# Sheet1.net
KiCad netlist of a schematic drawn in Altium Designer
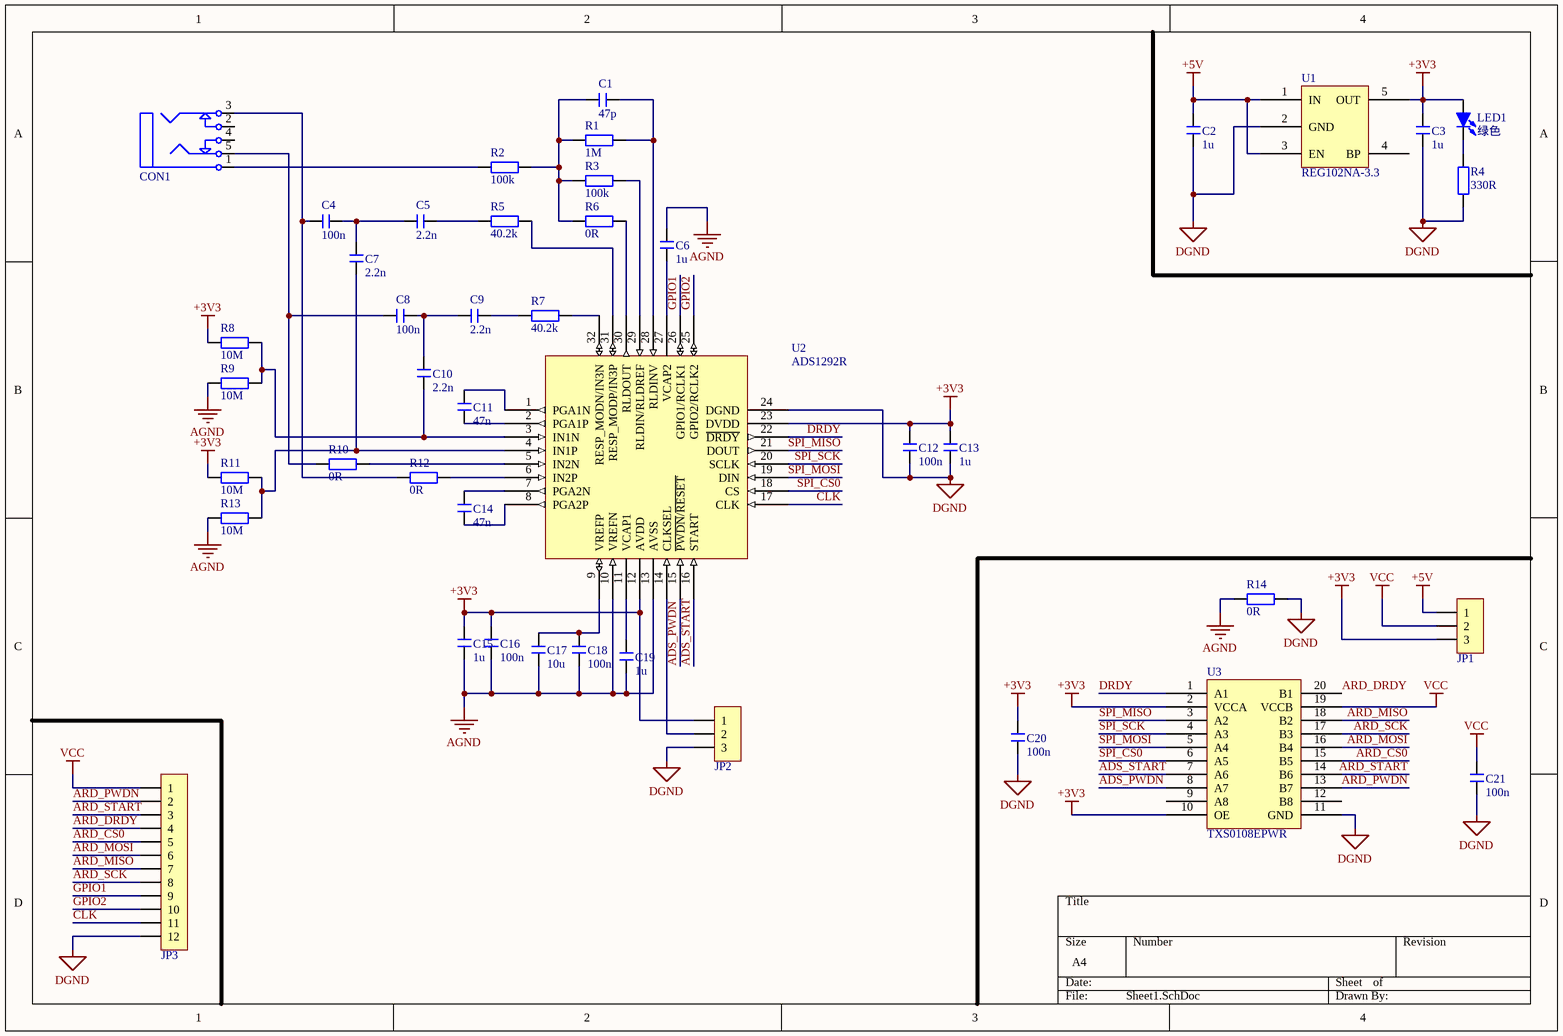
[diagram p0: Sheet1.SchDoc]

(export (version "E")
  (design (tool "Eeschema 10.0.6"))
  (components
    (comp (ref "C1")
      (value "47p")
      (footprint "C 0805_L")
      (description "无极性贴片电容")
      (fields (field (name "版权归属") "源创客"))
      (libsource (lib "3.1   - 电阻-电容-电感") (part "C"))
    )
    (comp (ref "C2")
      (value "1u")
      (footprint "C 0805_L")
      (description "无极性贴片电容")
      (fields (field (name "版权归属") "源创客"))
      (libsource (lib "3.1   - 电阻-电容-电感") (part "C"))
    )
    (comp (ref "C3")
      (value "1u")
      (footprint "C 0805_L")
      (description "无极性贴片电容")
      (fields (field (name "版权归属") "源创客"))
      (libsource (lib "3.1   - 电阻-电容-电感") (part "C"))
    )
    (comp (ref "C4")
      (value "100n")
      (footprint "C 0805_L")
      (description "无极性贴片电容")
      (fields (field (name "版权归属") "源创客"))
      (libsource (lib "3.1   - 电阻-电容-电感") (part "C"))
    )
    (comp (ref "C5")
      (value "2.2n")
      (footprint "C 0805_L")
      (description "无极性贴片电容")
      (fields (field (name "版权归属") "源创客"))
      (libsource (lib "3.1   - 电阻-电容-电感") (part "C"))
    )
    (comp (ref "C6")
      (value "1u")
      (footprint "C 0805_L")
      (description "无极性贴片电容")
      (fields (field (name "版权归属") "源创客"))
      (libsource (lib "3.1   - 电阻-电容-电感") (part "C"))
    )
    (comp (ref "C7")
      (value "2.2n")
      (footprint "C 0805_L")
      (description "无极性贴片电容")
      (fields (field (name "版权归属") "源创客"))
      (libsource (lib "3.1   - 电阻-电容-电感") (part "C"))
    )
    (comp (ref "C8")
      (value "100n")
      (footprint "C 0805_L")
      (description "无极性贴片电容")
      (fields (field (name "版权归属") "源创客"))
      (libsource (lib "3.1   - 电阻-电容-电感") (part "C"))
    )
    (comp (ref "C9")
      (value "2.2n")
      (footprint "C 0805_L")
      (description "无极性贴片电容")
      (fields (field (name "版权归属") "源创客"))
      (libsource (lib "3.1   - 电阻-电容-电感") (part "C"))
    )
    (comp (ref "C10")
      (value "2.2n")
      (footprint "C 0805_L")
      (description "无极性贴片电容")
      (fields (field (name "版权归属") "源创客"))
      (libsource (lib "3.1   - 电阻-电容-电感") (part "C"))
    )
    (comp (ref "C11")
      (value "47n")
      (footprint "C 0805_L")
      (description "无极性贴片电容")
      (fields (field (name "版权归属") "源创客"))
      (libsource (lib "3.1   - 电阻-电容-电感") (part "C"))
    )
    (comp (ref "C12")
      (value "100n")
      (footprint "C 0805_L")
      (description "无极性贴片电容")
      (fields (field (name "版权归属") "源创客"))
      (libsource (lib "3.1   - 电阻-电容-电感") (part "C"))
    )
    (comp (ref "C13")
      (value "1u")
      (footprint "C 0805_L")
      (description "无极性贴片电容")
      (fields (field (name "版权归属") "源创客"))
      (libsource (lib "3.1   - 电阻-电容-电感") (part "C"))
    )
    (comp (ref "C14")
      (value "47n")
      (footprint "C 0805_L")
      (description "无极性贴片电容")
      (fields (field (name "版权归属") "源创客"))
      (libsource (lib "3.1   - 电阻-电容-电感") (part "C"))
    )
    (comp (ref "C15")
      (value "1u")
      (footprint "C 0805_L")
      (description "无极性贴片电容")
      (fields (field (name "版权归属") "源创客"))
      (libsource (lib "3.1   - 电阻-电容-电感") (part "C"))
    )
    (comp (ref "C16")
      (value "100n")
      (footprint "C 0805_L")
      (description "无极性贴片电容")
      (fields (field (name "版权归属") "源创客"))
      (libsource (lib "3.1   - 电阻-电容-电感") (part "C"))
    )
    (comp (ref "C17")
      (value "10u")
      (footprint "C 0805_L")
      (description "无极性贴片电容")
      (fields (field (name "版权归属") "源创客"))
      (libsource (lib "3.1   - 电阻-电容-电感") (part "C"))
    )
    (comp (ref "C18")
      (value "100n")
      (footprint "C 0805_L")
      (description "无极性贴片电容")
      (fields (field (name "版权归属") "源创客"))
      (libsource (lib "3.1   - 电阻-电容-电感") (part "C"))
    )
    (comp (ref "C19")
      (value "1u")
      (footprint "C 0805_L")
      (description "无极性贴片电容")
      (fields (field (name "版权归属") "源创客"))
      (libsource (lib "3.1   - 电阻-电容-电感") (part "C"))
    )
    (comp (ref "C20")
      (value "100n")
      (footprint "C 0805_L")
      (description "无极性贴片电容")
      (fields (field (name "版权归属") "源创客"))
      (libsource (lib "3.1   - 电阻-电容-电感") (part "C"))
    )
    (comp (ref "C21")
      (value "100n")
      (footprint "C 0805_L")
      (description "无极性贴片电容")
      (fields (field (name "版权归属") "源创客"))
      (libsource (lib "3.1   - 电阻-电容-电感") (part "C"))
    )
    (comp (ref "CON1")
      (value "PJ325_BK")
      (footprint "PJ325_BK")
      (description "3.5mm耳机插座")
      (fields (field (name "版权归属") "源创客"))
      (libsource (lib "4.1   - 接口类") (part "PJ325"))
    )
    (comp (ref "JP1")
      (value "HDR-1X3")
      (footprint "HDR2.54-LI-3P")
      (description "3P接插件")
      (fields (field (name "版权归属") "源创客"))
      (libsource (lib "4.5   - 接插件-脚距2.54") (part "Header 3"))
    )
    (comp (ref "JP2")
      (value "HDR-1X3")
      (footprint "HDR2.54-LI-3P")
      (description "3P接插件")
      (fields (field (name "版权归属") "源创客"))
      (libsource (lib "4.5   - 接插件-脚距2.54") (part "Header 3"))
    )
    (comp (ref "JP3")
      (value "HDR-1X12")
      (footprint "HDR2.54-LI-12P")
      (description "12P接插件")
      (fields (field (name "版权归属") "源创客"))
      (libsource (lib "4.5   - 接插件-脚距2.54") (part "Header 12"))
    )
    (comp (ref "LED1")
      (value "绿色")
      (footprint "LED 0805G")
      (description "贴片LED")
      (fields (field (name "版权归属") "源创客"))
      (libsource (lib "9.1   - LED") (part "LED-SMD"))
    )
    (comp (ref "R1")
      (value "1M")
      (footprint "R 0805_L")
      (description "贴片电阻")
      (fields (field (name "版权归属") "源创客"))
      (libsource (lib "3.1   - 电阻-电容-电感") (part "R"))
    )
    (comp (ref "R2")
      (value "100k")
      (footprint "R 0805_L")
      (description "贴片电阻")
      (fields (field (name "版权归属") "源创客"))
      (libsource (lib "3.1   - 电阻-电容-电感") (part "R"))
    )
    (comp (ref "R3")
      (value "100k")
      (footprint "R 0805_L")
      (description "贴片电阻")
      (fields (field (name "版权归属") "源创客"))
      (libsource (lib "3.1   - 电阻-电容-电感") (part "R"))
    )
    (comp (ref "R4")
      (value "330R")
      (footprint "R 0805_L")
      (description "贴片电阻")
      (fields (field (name "版权归属") "源创客"))
      (libsource (lib "3.1   - 电阻-电容-电感") (part "R"))
    )
    (comp (ref "R5")
      (value "40.2k")
      (footprint "R 0805_L")
      (description "贴片电阻")
      (fields (field (name "版权归属") "源创客"))
      (libsource (lib "3.1   - 电阻-电容-电感") (part "R"))
    )
    (comp (ref "R6")
      (value "0R")
      (footprint "R 0805_L")
      (description "贴片电阻")
      (fields (field (name "版权归属") "源创客"))
      (libsource (lib "3.1   - 电阻-电容-电感") (part "R"))
    )
    (comp (ref "R7")
      (value "40.2k")
      (footprint "R 0805_L")
      (description "贴片电阻")
      (fields (field (name "版权归属") "源创客"))
      (libsource (lib "3.1   - 电阻-电容-电感") (part "R"))
    )
    (comp (ref "R8")
      (value "10M")
      (footprint "R 0805_L")
      (description "贴片电阻")
      (fields (field (name "版权归属") "源创客"))
      (libsource (lib "3.1   - 电阻-电容-电感") (part "R"))
    )
    (comp (ref "R9")
      (value "10M")
      (footprint "R 0805_L")
      (description "贴片电阻")
      (fields (field (name "版权归属") "源创客"))
      (libsource (lib "3.1   - 电阻-电容-电感") (part "R"))
    )
    (comp (ref "R10")
      (value "0R")
      (footprint "R 0805_L")
      (description "贴片电阻")
      (fields (field (name "版权归属") "源创客"))
      (libsource (lib "3.1   - 电阻-电容-电感") (part "R"))
    )
    (comp (ref "R11")
      (value "10M")
      (footprint "R 0805_L")
      (description "贴片电阻")
      (fields (field (name "版权归属") "源创客"))
      (libsource (lib "3.1   - 电阻-电容-电感") (part "R"))
    )
    (comp (ref "R12")
      (value "0R")
      (footprint "R 0805_L")
      (description "贴片电阻")
      (fields (field (name "版权归属") "源创客"))
      (libsource (lib "3.1   - 电阻-电容-电感") (part "R"))
    )
    (comp (ref "R13")
      (value "10M")
      (footprint "R 0805_L")
      (description "贴片电阻")
      (fields (field (name "版权归属") "源创客"))
      (libsource (lib "3.1   - 电阻-电容-电感") (part "R"))
    )
    (comp (ref "R14")
      (value "0R")
      (footprint "R 0805_L")
      (description "贴片电阻")
      (fields (field (name "版权归属") "源创客"))
      (libsource (lib "3.1   - 电阻-电容-电感") (part "R"))
    )
    (comp (ref "U1")
      (value "REG102NA-3.3")
      (footprint "REG102NA-3.3")
      (libsource (lib "Schlib1") (part "REG102NA-3.3"))
    )
    (comp (ref "U2") (value "ADS1292R") (footprint "ADS1292R") (libsource (lib "Schlib1") (part "ADS1292R")))
    (comp (ref "U3")
      (value "TXS0108EPWR")
      (footprint "TXS0108EPWR")
      (libsource (lib "Schlib1") (part "TXS0108EPWR"))
    )
  )
  (nets
    (net (code "1") (name "+3V3") (class "Default")
      (node (ref "C12") (pin "2") (pinfunction "2_2") (pintype "passive"))
      (node (ref "C13") (pin "1") (pinfunction "1_1") (pintype "passive"))
      (node (ref "C15") (pin "2") (pinfunction "2_2") (pintype "passive"))
      (node (ref "C16") (pin "2") (pinfunction "2_2") (pintype "passive"))
      (node (ref "C20") (pin "2") (pinfunction "2_2") (pintype "passive"))
      (node (ref "C3") (pin "2") (pinfunction "2_2") (pintype "passive"))
      (node (ref "JP1") (pin "3") (pinfunction "3_3") (pintype "passive"))
      (node (ref "JP2") (pin "1") (pinfunction "1_1") (pintype "passive"))
      (node (ref "LED1") (pin "1") (pinfunction "A_1") (pintype "passive"))
      (node (ref "R11") (pin "2") (pinfunction "2_2") (pintype "passive"))
      (node (ref "R8") (pin "2") (pinfunction "2_2") (pintype "passive"))
      (node (ref "U1") (pin "5") (pinfunction "OUT_5") (pintype "passive"))
      (node (ref "U2") (pin "12") (pinfunction "AVDD_12") (pintype "power_in"))
      (node (ref "U2") (pin "23") (pinfunction "DVDD_23") (pintype "power_in"))
      (node (ref "U3") (pin "10") (pinfunction "OE_10") (pintype "passive"))
      (node (ref "U3") (pin "2") (pinfunction "VCCA_2") (pintype "passive"))
    )
    (net (code "2") (name "+5V") (class "Default")
      (node (ref "C2") (pin "2") (pinfunction "2_2") (pintype "passive"))
      (node (ref "JP1") (pin "1") (pinfunction "1_1") (pintype "passive"))
      (node (ref "U1") (pin "1") (pinfunction "IN_1") (pintype "passive"))
      (node (ref "U1") (pin "3") (pinfunction "EN_3") (pintype "passive"))
    )
    (net (code "3") (name "/ADS_PWDN") (class "Default")
      (node (ref "U2") (pin "15") (pinfunction "~{PWDN}/~{RESET}_15") (pintype "input"))
      (node (ref "U3") (pin "8") (pinfunction "A7_8") (pintype "passive"))
    )
    (net (code "4") (name "/ADS_START") (class "Default")
      (node (ref "U2") (pin "16") (pinfunction "START_16") (pintype "input"))
      (node (ref "U3") (pin "7") (pinfunction "A6_7") (pintype "passive"))
    )
    (net (code "5") (name "/ARD_CS0") (class "Default")
      (node (ref "JP3") (pin "5") (pinfunction "5_5") (pintype "passive"))
      (node (ref "U3") (pin "15") (pinfunction "B5_15") (pintype "passive"))
    )
    (net (code "6") (name "/ARD_DRDY") (class "Default")
      (node (ref "JP3") (pin "4") (pinfunction "4_4") (pintype "passive"))
      (node (ref "U3") (pin "20") (pinfunction "B1_20") (pintype "passive"))
    )
    (net (code "7") (name "/ARD_MISO") (class "Default")
      (node (ref "JP3") (pin "7") (pinfunction "7_7") (pintype "passive"))
      (node (ref "U3") (pin "18") (pinfunction "B2_18") (pintype "passive"))
    )
    (net (code "8") (name "/ARD_MOSI") (class "Default")
      (node (ref "JP3") (pin "6") (pinfunction "6_6") (pintype "passive"))
      (node (ref "U3") (pin "16") (pinfunction "B4_16") (pintype "passive"))
    )
    (net (code "9") (name "/ARD_PWDN") (class "Default")
      (node (ref "JP3") (pin "2") (pinfunction "2_2") (pintype "passive"))
      (node (ref "U3") (pin "13") (pinfunction "B7_13") (pintype "passive"))
    )
    (net (code "10") (name "/ARD_SCK") (class "Default")
      (node (ref "JP3") (pin "8") (pinfunction "8_8") (pintype "passive"))
      (node (ref "U3") (pin "17") (pinfunction "B3_17") (pintype "passive"))
    )
    (net (code "11") (name "/ARD_START") (class "Default")
      (node (ref "JP3") (pin "3") (pinfunction "3_3") (pintype "passive"))
      (node (ref "U3") (pin "14") (pinfunction "B6_14") (pintype "passive"))
    )
    (net (code "12") (name "/CLK") (class "Default")
      (node (ref "JP3") (pin "11") (pinfunction "11_11") (pintype "passive"))
      (node (ref "U2") (pin "17") (pinfunction "CLK_17") (pintype "input"))
    )
    (net (code "13") (name "/DRDY") (class "Default")
      (node (ref "U2") (pin "22") (pinfunction "~{DRDY}_22") (pintype "output"))
      (node (ref "U3") (pin "1") (pinfunction "A1_1") (pintype "passive"))
    )
    (net (code "14") (name "/GPIO1") (class "Default")
      (node (ref "JP3") (pin "9") (pinfunction "9_9") (pintype "passive"))
      (node (ref "U2") (pin "26") (pinfunction "GPIO1/RCLK1_26") (pintype "bidirectional"))
    )
    (net (code "15") (name "/GPIO2") (class "Default")
      (node (ref "JP3") (pin "10") (pinfunction "10_10") (pintype "passive"))
      (node (ref "U2") (pin "25") (pinfunction "GPIO2/RCLK2_25") (pintype "bidirectional"))
    )
    (net (code "16") (name "/SPI_CS0") (class "Default")
      (node (ref "U2") (pin "18") (pinfunction "CS_18") (pintype "input"))
      (node (ref "U3") (pin "6") (pinfunction "A5_6") (pintype "passive"))
    )
    (net (code "17") (name "/SPI_MISO") (class "Default")
      (node (ref "U2") (pin "21") (pinfunction "DOUT_21") (pintype "output"))
      (node (ref "U3") (pin "3") (pinfunction "A2_3") (pintype "passive"))
    )
    (net (code "18") (name "/SPI_MOSI") (class "Default")
      (node (ref "U2") (pin "19") (pinfunction "DIN_19") (pintype "input"))
      (node (ref "U3") (pin "5") (pinfunction "A4_5") (pintype "passive"))
    )
    (net (code "19") (name "/SPI_SCK") (class "Default")
      (node (ref "U2") (pin "20") (pinfunction "SCLK_20") (pintype "input"))
      (node (ref "U3") (pin "4") (pinfunction "A3_4") (pintype "passive"))
    )
    (net (code "20") (name "AGND") (class "Default")
      (node (ref "C15") (pin "1") (pinfunction "1_1") (pintype "passive"))
      (node (ref "C16") (pin "1") (pinfunction "1_1") (pintype "passive"))
      (node (ref "C17") (pin "1") (pinfunction "1_1") (pintype "passive"))
      (node (ref "C18") (pin "1") (pinfunction "1_1") (pintype "passive"))
      (node (ref "C19") (pin "1") (pinfunction "1_1") (pintype "passive"))
      (node (ref "C6") (pin "2") (pinfunction "2_2") (pintype "passive"))
      (node (ref "R13") (pin "2") (pinfunction "2_2") (pintype "passive"))
      (node (ref "R14") (pin "1") (pinfunction "1_1") (pintype "passive"))
      (node (ref "R9") (pin "2") (pinfunction "2_2") (pintype "passive"))
      (node (ref "U2") (pin "10") (pinfunction "VREFN_10") (pintype "input"))
      (node (ref "U2") (pin "13") (pinfunction "AVSS_13") (pintype "power_in"))
    )
    (net (code "21") (name "DGND") (class "Default")
      (node (ref "C12") (pin "1") (pinfunction "1_1") (pintype "passive"))
      (node (ref "C13") (pin "2") (pinfunction "2_2") (pintype "passive"))
      (node (ref "C2") (pin "1") (pinfunction "1_1") (pintype "passive"))
      (node (ref "C20") (pin "1") (pinfunction "1_1") (pintype "passive"))
      (node (ref "C21") (pin "2") (pinfunction "2_2") (pintype "passive"))
      (node (ref "C3") (pin "1") (pinfunction "1_1") (pintype "passive"))
      (node (ref "JP2") (pin "3") (pinfunction "3_3") (pintype "passive"))
      (node (ref "JP3") (pin "12") (pinfunction "12_12") (pintype "passive"))
      (node (ref "R14") (pin "2") (pinfunction "2_2") (pintype "passive"))
      (node (ref "R4") (pin "1") (pinfunction "1_1") (pintype "passive"))
      (node (ref "U1") (pin "2") (pinfunction "GND_2") (pintype "passive"))
      (node (ref "U2") (pin "24") (pinfunction "DGND_24") (pintype "power_in"))
      (node (ref "U3") (pin "11") (pinfunction "GND_11") (pintype "passive"))
    )
    (net (code "22") (name "Net-(C1-Pad1)") (class "Default")
      (node (ref "C1") (pin "1") (pinfunction "1_1") (pintype "passive"))
      (node (ref "R1") (pin "1") (pinfunction "1_1") (pintype "passive"))
      (node (ref "R2") (pin "2") (pinfunction "2_2") (pintype "passive"))
      (node (ref "R3") (pin "1") (pinfunction "1_1") (pintype "passive"))
      (node (ref "R6") (pin "1") (pinfunction "1_1") (pintype "passive"))
    )
    (net (code "23") (name "Net-(C4-Pad1)") (class "Default")
      (node (ref "C4") (pin "1") (pinfunction "1_1") (pintype "passive"))
      (node (ref "CON1") (pin "3") (pinfunction "3_3") (pintype "passive"))
      (node (ref "R12") (pin "1") (pinfunction "1_1") (pintype "passive"))
    )
    (net (code "24") (name "Net-(C4-Pad2)") (class "Default")
      (node (ref "C4") (pin "2") (pinfunction "2_2") (pintype "passive"))
      (node (ref "C5") (pin "1") (pinfunction "1_1") (pintype "passive"))
      (node (ref "C7") (pin "2") (pinfunction "2_2") (pintype "passive"))
    )
    (net (code "25") (name "Net-(C5-Pad2)") (class "Default")
      (node (ref "C5") (pin "2") (pinfunction "2_2") (pintype "passive"))
      (node (ref "R5") (pin "1") (pinfunction "1_1") (pintype "passive"))
    )
    (net (code "26") (name "Net-(C8-Pad1)") (class "Default")
      (node (ref "C8") (pin "1") (pinfunction "1_1") (pintype "passive"))
      (node (ref "CON1") (pin "5") (pinfunction "5_5") (pintype "passive"))
      (node (ref "R10") (pin "1") (pinfunction "1_1") (pintype "passive"))
    )
    (net (code "27") (name "Net-(C9-Pad2)") (class "Default")
      (node (ref "C9") (pin "2") (pinfunction "2_2") (pintype "passive"))
      (node (ref "R7") (pin "1") (pinfunction "1_1") (pintype "passive"))
    )
    (net (code "28") (name "Net-(C10-Pad2)") (class "Default")
      (node (ref "C10") (pin "2") (pinfunction "2_2") (pintype "passive"))
      (node (ref "C8") (pin "2") (pinfunction "2_2") (pintype "passive"))
      (node (ref "C9") (pin "1") (pinfunction "1_1") (pintype "passive"))
    )
    (net (code "29") (name "Net-(CON1-Pad1)") (class "Default")
      (node (ref "CON1") (pin "1") (pinfunction "1_1") (pintype "passive"))
      (node (ref "R2") (pin "1") (pinfunction "1_1") (pintype "passive"))
    )
    (net (code "30") (name "Net-(LED1-K)") (class "Default")
      (node (ref "LED1") (pin "2") (pinfunction "K_2") (pintype "passive"))
      (node (ref "R4") (pin "2") (pinfunction "2_2") (pintype "passive"))
    )
    (net (code "31") (name "Net-(U2-CLKSEL)") (class "Default")
      (node (ref "JP2") (pin "2") (pinfunction "2_2") (pintype "passive"))
      (node (ref "U2") (pin "14") (pinfunction "CLKSEL_14") (pintype "input"))
    )
    (net (code "32") (name "Net-(U2-IN1N)") (class "Default")
      (node (ref "C10") (pin "1") (pinfunction "1_1") (pintype "passive"))
      (node (ref "R8") (pin "1") (pinfunction "1_1") (pintype "passive"))
      (node (ref "R9") (pin "1") (pinfunction "1_1") (pintype "passive"))
      (node (ref "U2") (pin "3") (pinfunction "IN1N_3") (pintype "input"))
    )
    (net (code "33") (name "Net-(U2-IN1P)") (class "Default")
      (node (ref "C7") (pin "1") (pinfunction "1_1") (pintype "passive"))
      (node (ref "R11") (pin "1") (pinfunction "1_1") (pintype "passive"))
      (node (ref "R13") (pin "1") (pinfunction "1_1") (pintype "passive"))
      (node (ref "U2") (pin "4") (pinfunction "IN1P_4") (pintype "input"))
    )
    (net (code "34") (name "Net-(U2-IN2N)") (class "Default")
      (node (ref "R10") (pin "2") (pinfunction "2_2") (pintype "passive"))
      (node (ref "U2") (pin "5") (pinfunction "IN2N_5") (pintype "input"))
    )
    (net (code "35") (name "Net-(U2-IN2P)") (class "Default")
      (node (ref "R12") (pin "2") (pinfunction "2_2") (pintype "passive"))
      (node (ref "U2") (pin "6") (pinfunction "IN2P_6") (pintype "input"))
    )
    (net (code "36") (name "Net-(U2-PGA1N)") (class "Default")
      (node (ref "C11") (pin "2") (pinfunction "2_2") (pintype "passive"))
      (node (ref "U2") (pin "1") (pinfunction "PGA1N_1") (pintype "output"))
    )
    (net (code "37") (name "Net-(U2-PGA1P)") (class "Default")
      (node (ref "C11") (pin "1") (pinfunction "1_1") (pintype "passive"))
      (node (ref "U2") (pin "2") (pinfunction "PGA1P_2") (pintype "output"))
    )
    (net (code "38") (name "Net-(U2-PGA2N)") (class "Default")
      (node (ref "C14") (pin "2") (pinfunction "2_2") (pintype "passive"))
      (node (ref "U2") (pin "7") (pinfunction "PGA2N_7") (pintype "output"))
    )
    (net (code "39") (name "Net-(U2-PGA2P)") (class "Default")
      (node (ref "C14") (pin "1") (pinfunction "1_1") (pintype "passive"))
      (node (ref "U2") (pin "8") (pinfunction "PGA2P_8") (pintype "output"))
    )
    (net (code "40") (name "Net-(U2-RESP_MODN{slash}IN3N)") (class "Default")
      (node (ref "R7") (pin "2") (pinfunction "2_2") (pintype "passive"))
      (node (ref "U2") (pin "32") (pinfunction "RESP_MODN/IN3N_32") (pintype "bidirectional"))
    )
    (net (code "41") (name "Net-(U2-RESP_MODP{slash}IN3P)") (class "Default")
      (node (ref "R5") (pin "2") (pinfunction "2_2") (pintype "passive"))
      (node (ref "U2") (pin "31") (pinfunction "RESP_MODP/IN3P_31") (pintype "bidirectional"))
    )
    (net (code "42") (name "Net-(U2-RLDINV)") (class "Default")
      (node (ref "C1") (pin "2") (pinfunction "2_2") (pintype "passive"))
      (node (ref "R1") (pin "2") (pinfunction "2_2") (pintype "passive"))
      (node (ref "U2") (pin "28") (pinfunction "RLDINV_28") (pintype "input"))
    )
    (net (code "43") (name "Net-(U2-RLDIN{slash}RLDREF)") (class "Default")
      (node (ref "R3") (pin "2") (pinfunction "2_2") (pintype "passive"))
      (node (ref "U2") (pin "29") (pinfunction "RLDIN/RLDREF_29") (pintype "input"))
    )
    (net (code "44") (name "Net-(U2-RLDOUT)") (class "Default")
      (node (ref "R6") (pin "2") (pinfunction "2_2") (pintype "passive"))
      (node (ref "U2") (pin "30") (pinfunction "RLDOUT_30") (pintype "output"))
    )
    (net (code "45") (name "Net-(U2-VCAP1)") (class "Default")
      (node (ref "C19") (pin "2") (pinfunction "2_2") (pintype "passive"))
      (node (ref "U2") (pin "11") (pinfunction "VCAP1_11") (pintype "passive"))
    )
    (net (code "46") (name "Net-(U2-VCAP2)") (class "Default")
      (node (ref "C6") (pin "1") (pinfunction "1_1") (pintype "passive"))
      (node (ref "U2") (pin "27") (pinfunction "VCAP2_27") (pintype "passive"))
    )
    (net (code "47") (name "Net-(U2-VREFP)") (class "Default")
      (node (ref "C17") (pin "2") (pinfunction "2_2") (pintype "passive"))
      (node (ref "C18") (pin "2") (pinfunction "2_2") (pintype "passive"))
      (node (ref "U2") (pin "9") (pinfunction "VREFP_9") (pintype "bidirectional"))
    )
    (net (code "48") (name "VCC") (class "Default")
      (node (ref "C21") (pin "1") (pinfunction "1_1") (pintype "passive"))
      (node (ref "JP1") (pin "2") (pinfunction "2_2") (pintype "passive"))
      (node (ref "JP3") (pin "1") (pinfunction "1_1") (pintype "passive"))
      (node (ref "U3") (pin "19") (pinfunction "VCCB_19") (pintype "passive"))
    )
    (net (code "49") (name "unconnected-(CON1-Pad2)") (class "Default")
      (node (ref "CON1") (pin "2") (pinfunction "2_2") (pintype "passive"))
    )
    (net (code "50") (name "unconnected-(CON1-Pad4)") (class "Default")
      (node (ref "CON1") (pin "4") (pinfunction "4_4") (pintype "passive"))
    )
    (net (code "51") (name "unconnected-(U1-BP-Pad4)") (class "Default")
      (node (ref "U1") (pin "4") (pinfunction "BP_4") (pintype "passive"))
    )
    (net (code "52") (name "unconnected-(U3-A8-Pad9)") (class "Default")
      (node (ref "U3") (pin "9") (pinfunction "A8_9") (pintype "passive"))
    )
    (net (code "53") (name "unconnected-(U3-B8-Pad12)") (class "Default")
      (node (ref "U3") (pin "12") (pinfunction "B8_12") (pintype "passive"))
    )
  )
)
